# Power.net
KiCad netlist of a schematic drawn in Altium Designer
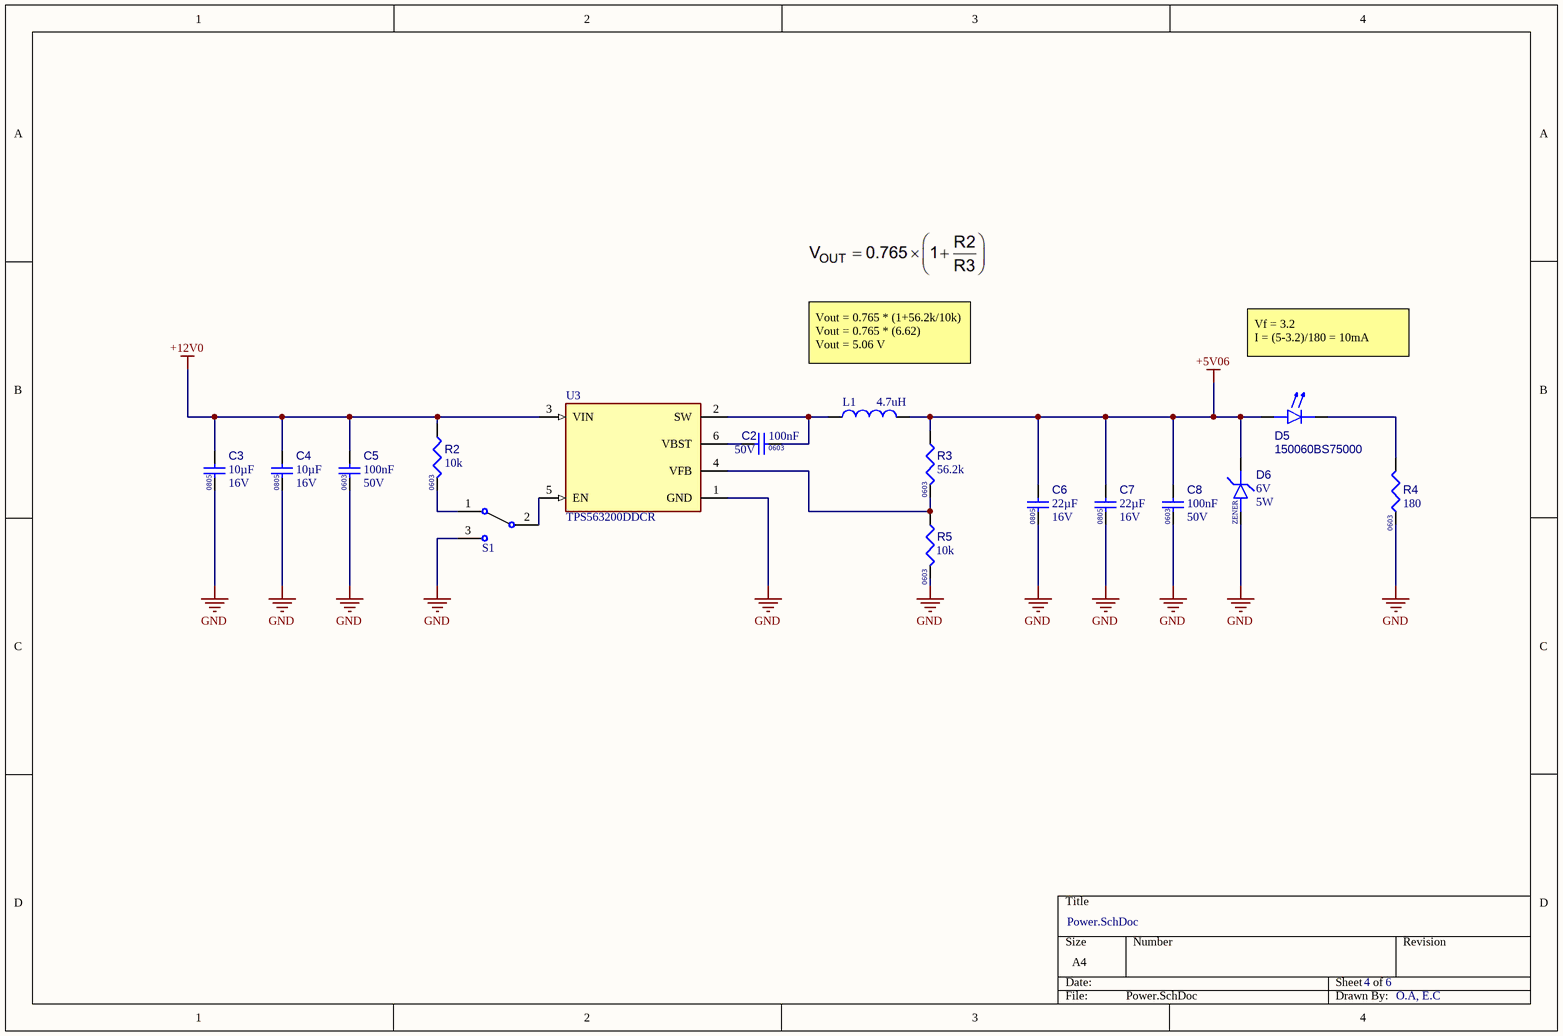
[diagram p0: Power.SchDoc]

(export (version "E")
  (design (tool "Eeschema 10.0.6"))
  (components
    (comp (ref "C2")
      (value "100nF")
      (footprint "CAPC1608X90X40NL10T20")
      (description "Chip Capacitor, 100 nF, +/- 10%, 50 V, 0603 (1608 Metric)")
      (fields
        (field (name "TOLERANCE") "10%")
        (field (name "VOLTAGE RATING") "50V")
        (field (name "CASE/PACKAGE") "0603")
        (field (name "Comment") "Capacitor 100 nF +/-10% 50 V 0603")
      )
      (libsource (lib "hawaiirobotics") (part "CAP-NP-2"))
    )
    (comp (ref "C3")
      (value "10µF")
      (footprint "CAP CER 10UF 16V X5R 0805-Footprint-1")
      (fields
        (field (name "VOLTAGE RATING") "16V")
        (field (name "CASE/PACKAGE") "0805")
        (field (name "Comment") "CAP CER 10UF 16V X5R 0805")
      )
      (libsource (lib "hawaiirobotics") (part "CAP-NP-2"))
    )
    (comp (ref "C4")
      (value "10µF")
      (footprint "CAP CER 10UF 16V X5R 0805-Footprint-1")
      (fields
        (field (name "VOLTAGE RATING") "16V")
        (field (name "CASE/PACKAGE") "0805")
        (field (name "Comment") "CAP CER 10UF 16V X5R 0805")
      )
      (libsource (lib "hawaiirobotics") (part "CAP-NP-2"))
    )
    (comp (ref "C5")
      (value "100nF")
      (footprint "CAPC1608X90X40NL10T20")
      (description "Chip Capacitor, 100 nF, +/- 10%, 50 V, 0603 (1608 Metric)")
      (fields
        (field (name "TOLERANCE") "10%")
        (field (name "VOLTAGE RATING") "50V")
        (field (name "CASE/PACKAGE") "0603")
        (field (name "Comment") "Capacitor 100 nF +/-10% 50 V 0603")
      )
      (libsource (lib "hawaiirobotics") (part "CAP-NP-2"))
    )
    (comp (ref "C6")
      (value "22µF")
      (footprint "CL21A226MOQNNNE-Footprint-1")
      (fields
        (field (name "VOLTAGE RATING") "16V")
        (field (name "CASE/PACKAGE") "0805")
        (field (name "Comment") "CL21A226MOQNNNE")
      )
      (libsource (lib "hawaiirobotics") (part "CAP-NP-2"))
    )
    (comp (ref "C7")
      (value "22µF")
      (footprint "CL21A226MOQNNNE-Footprint-1")
      (fields
        (field (name "VOLTAGE RATING") "16V")
        (field (name "CASE/PACKAGE") "0805")
        (field (name "Comment") "CL21A226MOQNNNE")
      )
      (libsource (lib "hawaiirobotics") (part "CAP-NP-2"))
    )
    (comp (ref "C8")
      (value "100nF")
      (footprint "CAPC1608X90X40NL10T20")
      (description "Chip Capacitor, 100 nF, +/- 10%, 50 V, 0603 (1608 Metric)")
      (fields
        (field (name "TOLERANCE") "10%")
        (field (name "VOLTAGE RATING") "50V")
        (field (name "CASE/PACKAGE") "0603")
        (field (name "Comment") "Capacitor 100 nF +/-10% 50 V 0603")
      )
      (libsource (lib "hawaiirobotics") (part "CAP-NP-2"))
    )
    (comp (ref "D5")
      (value "150060BS75000")
      (footprint "WL-SMCW_0603_150060xx75000")
      (description "Single Color LED, Blue, Water Clear, 1.1mm")
      (libsource (lib "hawaiirobotics") (part "DIODE-LED-2"))
    )
    (comp (ref "D6")
      (value "SMBJ5340B-TP")
      (footprint "FP-DO-214AA-MFG")
      (description "Zener Diode, 6V V(Z), 5%, 5W, Silicon, Unidirectional, DO-214AA")
      (fields
        (field (name "REFERENCE VOLTAGE-NOM") "6V")
        (field (name "MAX POWER DISSIPATION") "5W")
        (field (name "DIODE TYPE") "ZENER")
      )
      (libsource (lib "hawaiirobotics") (part "DIODE-2"))
    )
    (comp (ref "L1")
      (value "LQH5BPN4R7N38L")
      (footprint "FP-LQH5BPN_38-MFG")
      (description "General Purpose Inductor, 4.7uH, 30%, 1 Element, Ferrite-Core, SMD, 1919")
      (fields (field (name "TOLERANCE") "30%") (field (name "INDUCTANCE-NOM (L)") "4.7uH"))
      (libsource (lib "hawaiirobotics") (part "IND-2"))
    )
    (comp (ref "R2")
      (value "10k")
      (footprint "RESC1608X55X25NL10T15")
      (description "Chip Resistor, 10 KOhm, +/- 1%, 01 W, -55 to 155 degC, 0603 (1608 Metric)")
      (fields
        (field (name "CASE/PACKAGE") "0603")
        (field (name "POWER") "100mW")
        (field (name "TOLERANCE") "1%")
      )
      (libsource (lib "hawaiirobotics") (part "RES-2"))
    )
    (comp (ref "R3")
      (value "56.2k")
      (footprint "RC0603JR-0730KL-Footprint-1")
      (fields
        (field (name "TOLERANCE") "1%")
        (field (name "POWER") "100mW")
        (field (name "CASE/PACKAGE") "0603")
        (field (name "Comment") "RC0603FR-0756K2L")
      )
      (libsource (lib "hawaiirobotics") (part "RES-2"))
    )
    (comp (ref "R4")
      (value "180")
      (footprint "RESC0603(1608)_N")
      (fields
        (field (name "TOLERANCE") "5%")
        (field (name "CASE/PACKAGE") "0603")
        (field (name "POWER") "100mW")
        (field (name "Comment") "RC0603JR-07180RL")
      )
      (libsource (lib "hawaiirobotics") (part "RES-2"))
    )
    (comp (ref "R5")
      (value "10k")
      (footprint "RESC1608X55X25NL10T15")
      (description "Chip Resistor, 10 KOhm, +/- 1%, 01 W, -55 to 155 degC, 0603 (1608 Metric)")
      (fields
        (field (name "CASE/PACKAGE") "0603")
        (field (name "POWER") "100mW")
        (field (name "TOLERANCE") "1%")
      )
      (libsource (lib "hawaiirobotics") (part "RES-2"))
    )
    (comp (ref "S1")
      (value "SLW-883935-2A-D")
      (footprint "SLW-883935-2A-D-Footprint-1")
      (description "8.8 X 3.9 X 3.5 Mm, 2 Mm Raised")
      (libsource (lib "hawaiirobotics") (part "SLW-883935-2A-D-Symbol-1"))
    )
    (comp (ref "U3")
      (value "TPS563200DDCR")
      (footprint "FP-DDC0006A-MFG")
      (description "Switching Regulator, 3A, 650kHz Switching Freq-Max, PDSO6")
      (libsource (lib "hawaiirobotics") (part "31d0a13bcb823f7fa58c78a9b473f81"))
    )
  )
  (nets
    (net (code "1") (name "+5V06") (class "Default")
      (node (ref "C6") (pin "2") (pinfunction "2_2") (pintype "passive"))
      (node (ref "C7") (pin "2") (pinfunction "2_2") (pintype "passive"))
      (node (ref "C8") (pin "2") (pinfunction "2_2") (pintype "passive"))
      (node (ref "D5") (pin "2") (pinfunction "A_2") (pintype "passive"))
      (node (ref "D6") (pin "1") (pinfunction "K_1") (pintype "passive"))
      (node (ref "L1") (pin "1") (pinfunction "1_1") (pintype "passive"))
      (node (ref "R3") (pin "2") (pinfunction "2_2") (pintype "passive"))
    )
    (net (code "2") (name "+12V0") (class "Default")
      (node (ref "C3") (pin "2") (pinfunction "2_2") (pintype "passive"))
      (node (ref "C4") (pin "2") (pinfunction "2_2") (pintype "passive"))
      (node (ref "C5") (pin "2") (pinfunction "2_2") (pintype "passive"))
      (node (ref "R2") (pin "2") (pinfunction "2_2") (pintype "passive"))
      (node (ref "U3") (pin "3") (pinfunction "VIN_3") (pintype "input"))
    )
    (net (code "3") (name "GND") (class "Default")
      (node (ref "C3") (pin "1") (pinfunction "1_1") (pintype "passive"))
      (node (ref "C4") (pin "1") (pinfunction "1_1") (pintype "passive"))
      (node (ref "C5") (pin "1") (pinfunction "1_1") (pintype "passive"))
      (node (ref "C6") (pin "1") (pinfunction "1_1") (pintype "passive"))
      (node (ref "C7") (pin "1") (pinfunction "1_1") (pintype "passive"))
      (node (ref "C8") (pin "1") (pinfunction "1_1") (pintype "passive"))
      (node (ref "D6") (pin "2") (pinfunction "A_2") (pintype "passive"))
      (node (ref "R4") (pin "1") (pinfunction "1_1") (pintype "passive"))
      (node (ref "R5") (pin "1") (pinfunction "1_1") (pintype "passive"))
      (node (ref "S1") (pin "3") (pinfunction "NO_3") (pintype "passive"))
      (node (ref "U3") (pin "1") (pinfunction "GND_1") (pintype "power_in"))
    )
    (net (code "4") (name "Net-(D5-K)") (class "Default")
      (node (ref "D5") (pin "1") (pinfunction "K_1") (pintype "passive"))
      (node (ref "R4") (pin "2") (pinfunction "2_2") (pintype "passive"))
    )
    (net (code "5") (name "Net-(S1-COM)") (class "Default")
      (node (ref "S1") (pin "2") (pinfunction "COM_2") (pintype "passive"))
      (node (ref "U3") (pin "5") (pinfunction "EN_5") (pintype "input"))
    )
    (net (code "6") (name "Net-(S1-NC)") (class "Default")
      (node (ref "R2") (pin "1") (pinfunction "1_1") (pintype "passive"))
      (node (ref "S1") (pin "1") (pinfunction "NC_1") (pintype "passive"))
    )
    (net (code "7") (name "Net-(U3-SW)") (class "Default")
      (node (ref "C2") (pin "1") (pinfunction "1_1") (pintype "passive"))
      (node (ref "L1") (pin "2") (pinfunction "2_2") (pintype "passive"))
      (node (ref "U3") (pin "2") (pinfunction "SW_2") (pintype "passive"))
    )
    (net (code "8") (name "Net-(U3-VBST)") (class "Default")
      (node (ref "C2") (pin "2") (pinfunction "2_2") (pintype "passive"))
      (node (ref "U3") (pin "6") (pinfunction "VBST_6") (pintype "passive"))
    )
    (net (code "9") (name "Net-(U3-VFB)") (class "Default")
      (node (ref "R3") (pin "1") (pinfunction "1_1") (pintype "passive"))
      (node (ref "R5") (pin "2") (pinfunction "2_2") (pintype "passive"))
      (node (ref "U3") (pin "4") (pinfunction "VFB_4") (pintype "passive"))
    )
  )
)
